# Main.net
KiCad netlist of a schematic drawn in Altium Designer
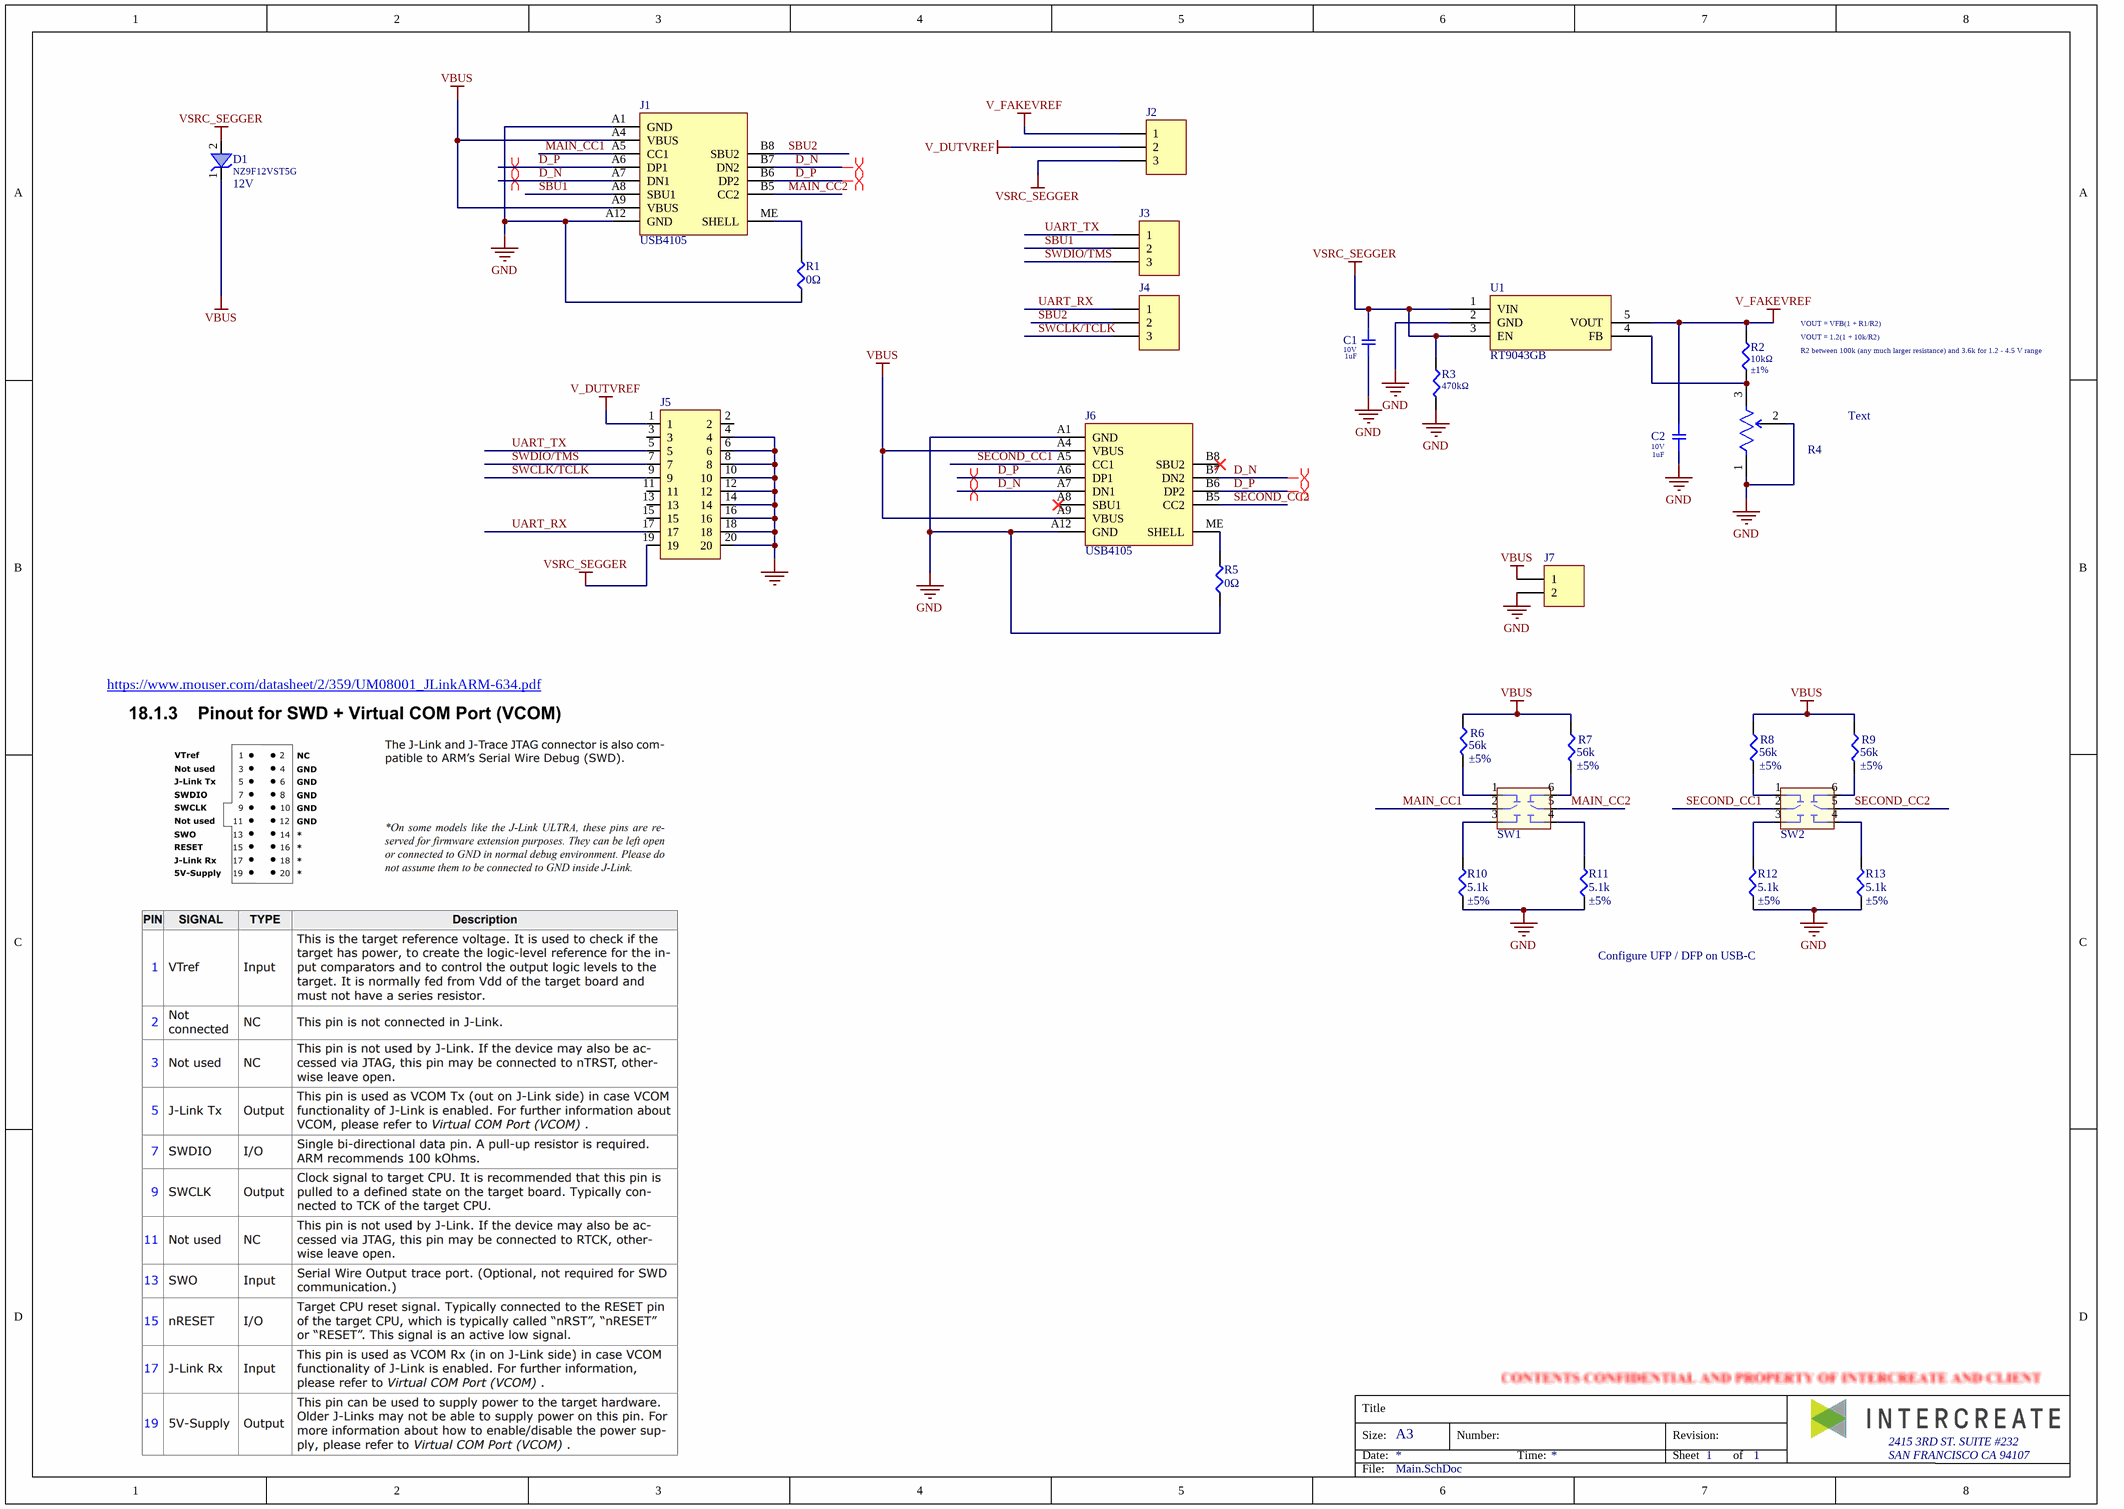
[diagram p0: Main.SchDoc]

(export (version "E")
  (design (tool "Eeschema 10.0.6"))
  (components
    (comp (ref "C1")
      (value "0402ZD105KAT2A")
      (footprint "CAP-0402")
      (fields
        (field (name "TOLERANCE") "10%")
        (field (name "VOLTAGE") "10V")
        (field (name "VOLTAGE RATING") "10V")
        (field (name "CAPACITANCE") "1uF")
      )
      (libsource (lib "intercreate") (part "CAP-1uF-10V-0402"))
    )
    (comp (ref "C2")
      (value "0402ZD105KAT2A")
      (footprint "CAP-0402")
      (fields
        (field (name "TOLERANCE") "10%")
        (field (name "VOLTAGE") "10V")
        (field (name "VOLTAGE RATING") "10V")
        (field (name "CAPACITANCE") "1uF")
      )
      (libsource (lib "intercreate") (part "CAP-1uF-10V-0402"))
    )
    (comp (ref "D1")
      (value "NZ9F12VST5G")
      (footprint "DIODE-SOD923")
      (description "DIODE ZENER 12V 200MW SOD923")
      (fields (field (name "TOLERANCE") "2%") (field (name "ZENER VOLTAGE") "12V"))
      (libsource (lib "intercreate") (part "DIODE-ZNR-12V-SOD923"))
    )
    (comp (ref "J1")
      (value "USB4105")
      (footprint "CONN-USBC-GCT_USB4105")
      (description "Usb Conn, 2.0 Type C, Rcpt, 16Pos, Smt Rohs Compliant: Yes")
      (libsource (lib "intercreate") (part "CONN-F-USB-C-GCT_USB4105"))
    )
    (comp (ref "J2")
      (value "61300311121")
      (footprint "HDR-V-1X3")
      (description "Header, 3-Pin, 0.1\"")
      (fields (field (name "MANUFACTURER") "Wurth Electronics") (field (name "PUBLISHER") "Altium Limited"))
      (libsource (lib "intercreate") (part "HDR-V-1X3-M"))
    )
    (comp (ref "J3")
      (value "61300311121")
      (footprint "HDR-V-1X3")
      (description "Header, 3-Pin, 0.1\"")
      (fields (field (name "MANUFACTURER") "Wurth Electronics") (field (name "PUBLISHER") "Altium Limited"))
      (libsource (lib "intercreate") (part "HDR-V-1X3-M"))
    )
    (comp (ref "J4")
      (value "61300311121")
      (footprint "HDR-V-1X3")
      (description "Header, 3-Pin, 0.1\"")
      (fields (field (name "MANUFACTURER") "Wurth Electronics") (field (name "PUBLISHER") "Altium Limited"))
      (libsource (lib "intercreate") (part "HDR-V-1X3-M"))
    )
    (comp (ref "J5")
      (value "SFH11-PBPC-D10-ST-BK")
      (footprint "HDR-V-2X10-F-2.54MM")
      (description "20 Position Header Connector 0.100\" (2.54mm) Through Hole Gold")
      (libsource (lib "intercreate") (part "HDR-V-2X10-F-2.54MM"))
    )
    (comp (ref "J6")
      (value "USB4105")
      (footprint "CONN-USBC-GCT_USB4105")
      (description "Usb Conn, 2.0 Type C, Rcpt, 16Pos, Smt Rohs Compliant: Yes")
      (libsource (lib "intercreate") (part "CONN-F-USB-C-GCT_USB4105"))
    )
    (comp (ref "J7")
      (value "61300211121")
      (footprint "HDR-V-1X2")
      (description "Header, 2-Pin, 0.1\"")
      (fields (field (name "MANUFACTURER") "Wurth Electronics") (field (name "PUBLISHER") "Altium Limited"))
      (libsource (lib "intercreate") (part "HDR-V-1X2-M"))
    )
    (comp (ref "R1")
      (value "0Ω")
      (footprint "RES-0402")
      (description "RES 0 OHM JUMPER 1/16W 0402")
      (fields
        (field (name "MANUFACTURER") "Yageo")
        (field (name "MANUFACTURER PART NUMBER") "RC0402FR-070RL")
      )
      (libsource (lib "intercreate") (part "RES-0-0402"))
    )
    (comp (ref "R2")
      (value "10kΩ")
      (footprint "RES-0402")
      (description "RES SMD 10K OHM 1% 1/16W 0402")
      (fields (field (name "TOLERANCE") "±1%") (field (name "Comment") "RC0402FR-0710KL"))
      (libsource (lib "intercreate") (part "RES-10K-0402"))
    )
    (comp (ref "R3")
      (value "470kΩ")
      (footprint "RES-0402")
      (description "RES SMD 470K OHM 1% 1/16W 0402")
      (fields (field (name "TOLERANCE") "1%") (field (name "Comment") "RES-470K-0402"))
      (libsource (lib "Intercreate") (part "RES-95.3K-0402-0.1"))
    )
    (comp (ref "R4")
      (value "POT-ROT-100K-SMD")
      (footprint "3361P-1-104GLF")
      (description "TRIMMER 100K OHM 0.5W GW TOP ADJ")
      (libsource (lib "intercreate") (part "POT-ROT-100K-SMD"))
    )
    (comp (ref "R5")
      (value "0Ω")
      (footprint "RES-0402")
      (description "RES 0 OHM JUMPER 1/16W 0402")
      (fields
        (field (name "MANUFACTURER") "Yageo")
        (field (name "MANUFACTURER PART NUMBER") "RC0402FR-070RL")
      )
      (libsource (lib "intercreate") (part "RES-0-0402"))
    )
    (comp (ref "R6")
      (value "56k")
      (footprint "RES-0402")
      (description "RES SMD 56K OHM 5% 1/10W 0402")
      (fields
        (field (name "MANUFACTURER") "Panasonic")
        (field (name "MANUFACTURER PART NUMBER") "ERJ2GEJ563X")
        (field (name "TOLERANCE") "±5%")
      )
      (libsource (lib "intercreate") (part "RES-56K-0402-5%"))
    )
    (comp (ref "R7")
      (value "56k")
      (footprint "RES-0402")
      (description "RES SMD 56K OHM 5% 1/10W 0402")
      (fields
        (field (name "MANUFACTURER") "Panasonic")
        (field (name "MANUFACTURER PART NUMBER") "ERJ2GEJ563X")
        (field (name "TOLERANCE") "±5%")
      )
      (libsource (lib "intercreate") (part "RES-56K-0402-5%"))
    )
    (comp (ref "R8")
      (value "56k")
      (footprint "RES-0402")
      (description "RES SMD 56K OHM 5% 1/10W 0402")
      (fields
        (field (name "MANUFACTURER") "Panasonic")
        (field (name "MANUFACTURER PART NUMBER") "ERJ2GEJ563X")
        (field (name "TOLERANCE") "±5%")
      )
      (libsource (lib "intercreate") (part "RES-56K-0402-5%"))
    )
    (comp (ref "R9")
      (value "56k")
      (footprint "RES-0402")
      (description "RES SMD 56K OHM 5% 1/10W 0402")
      (fields
        (field (name "MANUFACTURER") "Panasonic")
        (field (name "MANUFACTURER PART NUMBER") "ERJ2GEJ563X")
        (field (name "TOLERANCE") "±5%")
      )
      (libsource (lib "intercreate") (part "RES-56K-0402-5%"))
    )
    (comp (ref "R10")
      (value "5.1k")
      (footprint "RES-0402")
      (description "RES SMD 5.1K OHM 5% 1/10W 0402")
      (fields (field (name "TOLERANCE") "±5%") (field (name "Comment") "ERJ2GEJ512X"))
      (libsource (lib "intercreate") (part "RES-5.1K-0402"))
    )
    (comp (ref "R11")
      (value "5.1k")
      (footprint "RES-0402")
      (description "RES SMD 5.1K OHM 5% 1/10W 0402")
      (fields (field (name "TOLERANCE") "±5%") (field (name "Comment") "ERJ2GEJ512X"))
      (libsource (lib "intercreate") (part "RES-5.1K-0402"))
    )
    (comp (ref "R12")
      (value "5.1k")
      (footprint "RES-0402")
      (description "RES SMD 5.1K OHM 5% 1/10W 0402")
      (fields (field (name "TOLERANCE") "±5%") (field (name "Comment") "ERJ2GEJ512X"))
      (libsource (lib "intercreate") (part "RES-5.1K-0402"))
    )
    (comp (ref "R13")
      (value "5.1k")
      (footprint "RES-0402")
      (description "RES SMD 5.1K OHM 5% 1/10W 0402")
      (fields (field (name "TOLERANCE") "±5%") (field (name "Comment") "ERJ2GEJ512X"))
      (libsource (lib "intercreate") (part "RES-5.1K-0402"))
    )
    (comp (ref "SW1")
      (value "CS-4-22YTA")
      (footprint "SW-BCD-CS-4-22YTA")
      (description "SWITCH ROTARY DIP DPDT 100MA 16V")
      (fields (field (name "MANUFACTURER") "Nidec Copal"))
      (libsource (lib "intercreate") (part "SW-DPDT-3P-ROTARY"))
    )
    (comp (ref "SW2")
      (value "CS-4-22YTA")
      (footprint "SW-BCD-CS-4-22YTA")
      (description "SWITCH ROTARY DIP DPDT 100MA 16V")
      (fields (field (name "MANUFACTURER") "Nidec Copal"))
      (libsource (lib "intercreate") (part "SW-DPDT-3P-ROTARY"))
    )
    (comp (ref "U1")
      (value "RT9043GB")
      (footprint "SOT-23-5")
      (description "IC REG LINEAR 3.3V 400mA SOT23-5")
      (libsource (lib "intercreate") (part "IC-PWR-LDO-RT9043GB"))
    )
  )
  (nets
    (net (code "1") (name "/D_N") (class "Default")
      (node (ref "J1") (pin "A7") (pinfunction "DN1_A7") (pintype "passive"))
      (node (ref "J1") (pin "B7") (pinfunction "DN2_B7") (pintype "passive"))
      (node (ref "J6") (pin "A7") (pinfunction "DN1_A7") (pintype "passive"))
      (node (ref "J6") (pin "B7") (pinfunction "DN2_B7") (pintype "passive"))
    )
    (net (code "2") (name "/D_P") (class "Default")
      (node (ref "J1") (pin "A6") (pinfunction "DP1_A6") (pintype "passive"))
      (node (ref "J1") (pin "B6") (pinfunction "DP2_B6") (pintype "passive"))
      (node (ref "J6") (pin "A6") (pinfunction "DP1_A6") (pintype "passive"))
      (node (ref "J6") (pin "B6") (pinfunction "DP2_B6") (pintype "passive"))
    )
    (net (code "3") (name "/MAIN_CC1") (class "Default")
      (node (ref "J1") (pin "A5") (pinfunction "CC1_A5") (pintype "passive"))
      (node (ref "SW1") (pin "2") (pinfunction "2_2") (pintype "passive"))
    )
    (net (code "4") (name "/MAIN_CC2") (class "Default")
      (node (ref "J1") (pin "B5") (pinfunction "CC2_B5") (pintype "passive"))
      (node (ref "SW1") (pin "5") (pinfunction "5_5") (pintype "passive"))
    )
    (net (code "5") (name "/SBU1") (class "Default")
      (node (ref "J1") (pin "A8") (pinfunction "SBU1_A8") (pintype "passive"))
      (node (ref "J3") (pin "2") (pinfunction "2_2") (pintype "passive"))
    )
    (net (code "6") (name "/SBU2") (class "Default")
      (node (ref "J1") (pin "B8") (pinfunction "SBU2_B8") (pintype "passive"))
      (node (ref "J4") (pin "2") (pinfunction "2_2") (pintype "passive"))
    )
    (net (code "7") (name "/SECOND_CC1") (class "Default")
      (node (ref "J6") (pin "A5") (pinfunction "CC1_A5") (pintype "passive"))
      (node (ref "SW2") (pin "2") (pinfunction "2_2") (pintype "passive"))
    )
    (net (code "8") (name "/SECOND_CC2") (class "Default")
      (node (ref "J6") (pin "B5") (pinfunction "CC2_B5") (pintype "passive"))
      (node (ref "SW2") (pin "5") (pinfunction "5_5") (pintype "passive"))
    )
    (net (code "9") (name "/SWCLK{slash}TCLK") (class "Default")
      (node (ref "J4") (pin "3") (pinfunction "3_3") (pintype "passive"))
      (node (ref "J5") (pin "9") (pinfunction "9_9") (pintype "passive"))
    )
    (net (code "10") (name "/SWDIO{slash}TMS") (class "Default")
      (node (ref "J3") (pin "3") (pinfunction "3_3") (pintype "passive"))
      (node (ref "J5") (pin "7") (pinfunction "7_7") (pintype "passive"))
    )
    (net (code "11") (name "/UART_RX") (class "Default")
      (node (ref "J4") (pin "1") (pinfunction "1_1") (pintype "passive"))
      (node (ref "J5") (pin "17") (pinfunction "17_17") (pintype "passive"))
    )
    (net (code "12") (name "/UART_TX") (class "Default")
      (node (ref "J3") (pin "1") (pinfunction "1_1") (pintype "passive"))
      (node (ref "J5") (pin "5") (pinfunction "5_5") (pintype "passive"))
    )
    (net (code "13") (name "GND") (class "Default")
      (node (ref "C1") (pin "1") (pinfunction "1_1") (pintype "passive"))
      (node (ref "C2") (pin "1") (pinfunction "1_1") (pintype "passive"))
      (node (ref "J1") (pin "A1") (pinfunction "GND_A1") (pintype "passive"))
      (node (ref "J1") (pin "A12") (pinfunction "GND_A12") (pintype "passive"))
      (node (ref "J5") (pin "10") (pinfunction "10_10") (pintype "passive"))
      (node (ref "J5") (pin "12") (pinfunction "12_12") (pintype "passive"))
      (node (ref "J5") (pin "14") (pinfunction "14_14") (pintype "passive"))
      (node (ref "J5") (pin "16") (pinfunction "16_16") (pintype "passive"))
      (node (ref "J5") (pin "18") (pinfunction "18_18") (pintype "passive"))
      (node (ref "J5") (pin "20") (pinfunction "20_20") (pintype "passive"))
      (node (ref "J5") (pin "4") (pinfunction "4_4") (pintype "passive"))
      (node (ref "J5") (pin "6") (pinfunction "6_6") (pintype "passive"))
      (node (ref "J5") (pin "8") (pinfunction "8_8") (pintype "passive"))
      (node (ref "J6") (pin "A1") (pinfunction "GND_A1") (pintype "passive"))
      (node (ref "J6") (pin "A12") (pinfunction "GND_A12") (pintype "passive"))
      (node (ref "J7") (pin "2") (pinfunction "2_2") (pintype "passive"))
      (node (ref "R1") (pin "1") (pinfunction "1_1") (pintype "passive"))
      (node (ref "R10") (pin "1") (pinfunction "1_1") (pintype "passive"))
      (node (ref "R11") (pin "1") (pinfunction "1_1") (pintype "passive"))
      (node (ref "R12") (pin "1") (pinfunction "1_1") (pintype "passive"))
      (node (ref "R13") (pin "1") (pinfunction "1_1") (pintype "passive"))
      (node (ref "R3") (pin "2") (pinfunction "2_2") (pintype "passive"))
      (node (ref "R4") (pin "1") (pinfunction "CCW_1") (pintype "passive"))
      (node (ref "R4") (pin "2") (pinfunction "WIPER_2") (pintype "passive"))
      (node (ref "R5") (pin "1") (pinfunction "1_1") (pintype "passive"))
      (node (ref "U1") (pin "2") (pinfunction "GND_2") (pintype "passive"))
    )
    (net (code "14") (name "Net-(J1-SHELL)") (class "Default")
      (node (ref "J1") (pin "ME") (pinfunction "SHELL_ME") (pintype "passive"))
      (node (ref "R1") (pin "2") (pinfunction "2_2") (pintype "passive"))
    )
    (net (code "15") (name "Net-(J6-SHELL)") (class "Default")
      (node (ref "J6") (pin "ME") (pinfunction "SHELL_ME") (pintype "passive"))
      (node (ref "R5") (pin "2") (pinfunction "2_2") (pintype "passive"))
    )
    (net (code "16") (name "Net-(R4-CW)") (class "Default")
      (node (ref "R2") (pin "1") (pinfunction "1_1") (pintype "passive"))
      (node (ref "R4") (pin "3") (pinfunction "CW_3") (pintype "passive"))
      (node (ref "U1") (pin "4") (pinfunction "FB_4") (pintype "passive"))
    )
    (net (code "17") (name "Net-(R6-Pad2)") (class "Default")
      (node (ref "R6") (pin "2") (pinfunction "2_2") (pintype "passive"))
      (node (ref "SW1") (pin "1") (pinfunction "1_1") (pintype "passive"))
    )
    (net (code "18") (name "Net-(R7-Pad2)") (class "Default")
      (node (ref "R7") (pin "2") (pinfunction "2_2") (pintype "passive"))
      (node (ref "SW1") (pin "6") (pinfunction "6_6") (pintype "passive"))
    )
    (net (code "19") (name "Net-(R8-Pad2)") (class "Default")
      (node (ref "R8") (pin "2") (pinfunction "2_2") (pintype "passive"))
      (node (ref "SW2") (pin "1") (pinfunction "1_1") (pintype "passive"))
    )
    (net (code "20") (name "Net-(R9-Pad2)") (class "Default")
      (node (ref "R9") (pin "2") (pinfunction "2_2") (pintype "passive"))
      (node (ref "SW2") (pin "6") (pinfunction "6_6") (pintype "passive"))
    )
    (net (code "21") (name "Net-(R10-Pad2)") (class "Default")
      (node (ref "R10") (pin "2") (pinfunction "2_2") (pintype "passive"))
      (node (ref "SW1") (pin "3") (pinfunction "3_3") (pintype "passive"))
    )
    (net (code "22") (name "Net-(R11-Pad2)") (class "Default")
      (node (ref "R11") (pin "2") (pinfunction "2_2") (pintype "passive"))
      (node (ref "SW1") (pin "4") (pinfunction "4_4") (pintype "passive"))
    )
    (net (code "23") (name "Net-(R12-Pad2)") (class "Default")
      (node (ref "R12") (pin "2") (pinfunction "2_2") (pintype "passive"))
      (node (ref "SW2") (pin "3") (pinfunction "3_3") (pintype "passive"))
    )
    (net (code "24") (name "Net-(R13-Pad2)") (class "Default")
      (node (ref "R13") (pin "2") (pinfunction "2_2") (pintype "passive"))
      (node (ref "SW2") (pin "4") (pinfunction "4_4") (pintype "passive"))
    )
    (net (code "25") (name "VBUS") (class "Default")
      (node (ref "D1") (pin "1") (pinfunction "K_1") (pintype "passive"))
      (node (ref "J1") (pin "A4") (pinfunction "VBUS_A4") (pintype "passive"))
      (node (ref "J1") (pin "A9") (pinfunction "VBUS_A9") (pintype "passive"))
      (node (ref "J6") (pin "A4") (pinfunction "VBUS_A4") (pintype "passive"))
      (node (ref "J6") (pin "A9") (pinfunction "VBUS_A9") (pintype "passive"))
      (node (ref "J7") (pin "1") (pinfunction "1_1") (pintype "passive"))
      (node (ref "R6") (pin "1") (pinfunction "1_1") (pintype "passive"))
      (node (ref "R7") (pin "1") (pinfunction "1_1") (pintype "passive"))
      (node (ref "R8") (pin "1") (pinfunction "1_1") (pintype "passive"))
      (node (ref "R9") (pin "1") (pinfunction "1_1") (pintype "passive"))
    )
    (net (code "26") (name "VSRC_SEGGER") (class "Default")
      (node (ref "C1") (pin "2") (pinfunction "2_2") (pintype "passive"))
      (node (ref "D1") (pin "2") (pinfunction "A_2") (pintype "passive"))
      (node (ref "J2") (pin "3") (pinfunction "3_3") (pintype "passive"))
      (node (ref "J5") (pin "19") (pinfunction "19_19") (pintype "passive"))
      (node (ref "R3") (pin "1") (pinfunction "1_1") (pintype "passive"))
      (node (ref "U1") (pin "1") (pinfunction "VIN_1") (pintype "passive"))
      (node (ref "U1") (pin "3") (pinfunction "EN_3") (pintype "passive"))
    )
    (net (code "27") (name "V_DUTVREF") (class "Default")
      (node (ref "J2") (pin "2") (pinfunction "2_2") (pintype "passive"))
      (node (ref "J5") (pin "1") (pinfunction "1_1") (pintype "passive"))
    )
    (net (code "28") (name "V_FAKEVREF") (class "Default")
      (node (ref "C2") (pin "2") (pinfunction "2_2") (pintype "passive"))
      (node (ref "J2") (pin "1") (pinfunction "1_1") (pintype "passive"))
      (node (ref "R2") (pin "2") (pinfunction "2_2") (pintype "passive"))
      (node (ref "U1") (pin "5") (pinfunction "VOUT_5") (pintype "passive"))
    )
    (net (code "29") (name "unconnected-(J5-Pad2)") (class "Default")
      (node (ref "J5") (pin "2") (pinfunction "2_2") (pintype "passive"))
    )
    (net (code "30") (name "unconnected-(J5-Pad3)") (class "Default")
      (node (ref "J5") (pin "3") (pinfunction "3_3") (pintype "passive"))
    )
    (net (code "31") (name "unconnected-(J5-Pad11)") (class "Default")
      (node (ref "J5") (pin "11") (pinfunction "11_11") (pintype "passive"))
    )
    (net (code "32") (name "unconnected-(J5-Pad13)") (class "Default")
      (node (ref "J5") (pin "13") (pinfunction "13_13") (pintype "passive"))
    )
    (net (code "33") (name "unconnected-(J5-Pad15)") (class "Default")
      (node (ref "J5") (pin "15") (pinfunction "15_15") (pintype "passive"))
    )
    (net (code "34") (name "unconnected-(J6-SBU1-PadA8)") (class "Default")
      (node (ref "J6") (pin "A8") (pinfunction "SBU1_A8") (pintype "passive+no_connect"))
    )
    (net (code "35") (name "unconnected-(J6-SBU2-PadB8)") (class "Default")
      (node (ref "J6") (pin "B8") (pinfunction "SBU2_B8") (pintype "passive+no_connect"))
    )
  )
)
